# Tracksoar_programmer_shield.net
KiCad netlist of a schematic drawn in EAGLE
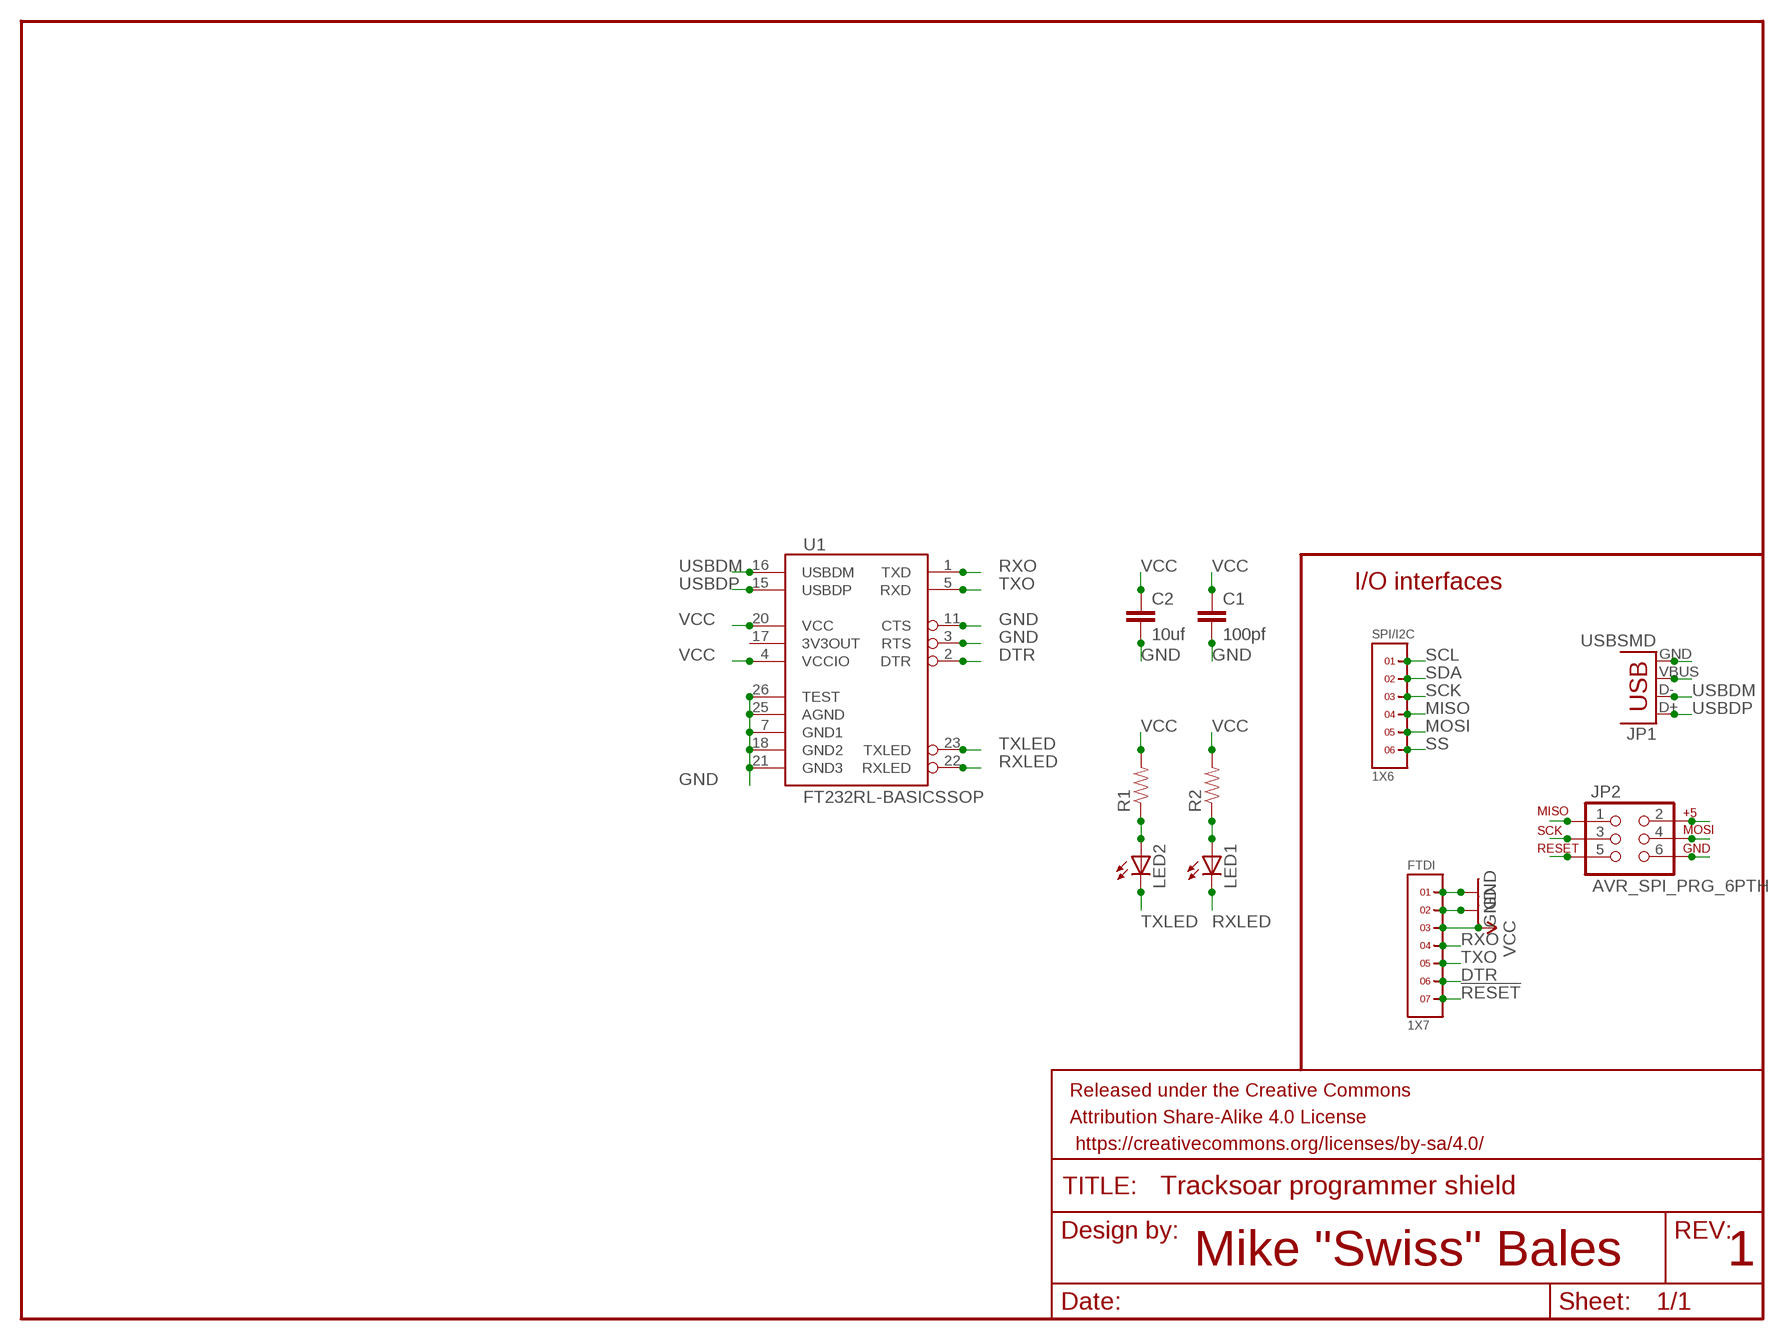
[diagram p0: schematic, sheet 1]

(export (version "E")
  (design (tool "Eeschema 10.0.6"))
  (components
    (comp (ref "C1")
      (value "100pf")
      (footprint "eagle-import:0805")
      (libsource (lib "eagle-import") (part "CAP0805"))
    )
    (comp (ref "C2")
      (value "10uf")
      (footprint "eagle-import:0805")
      (libsource (lib "eagle-import") (part "CAP0805"))
    )
    (comp (ref "FRAME1")
      (value "FRAME-LETTER")
      (footprint "eagle-import:CREATIVE_COMMONS")
      (libsource (lib "eagle-import") (part "FRAME-LETTER"))
    )
    (comp (ref "FTDI")
      (value "1X7")
      (footprint "eagle-import:1X7")
      (libsource (lib "eagle-import") (part "1X7"))
    )
    (comp (ref "JP1")
      (value "USBSMD")
      (footprint "eagle-import:USB-MINIB")
      (libsource (lib "eagle-import") (part "USBSMD"))
    )
    (comp (ref "JP2")
      (value "AVR_SPI_PRG_6PTH")
      (footprint "eagle-import:2X3")
      (libsource (lib "eagle-import") (part "AVR_SPI_PRG_6PTH"))
    )
    (comp (ref "LED1")
      (value "LEDCHIP-LED0805")
      (footprint "eagle-import:CHIP-LED0805")
      (libsource (lib "eagle-import") (part "LEDCHIP-LED0805"))
    )
    (comp (ref "LED2")
      (value "LEDCHIP-LED0805")
      (footprint "eagle-import:CHIP-LED0805")
      (libsource (lib "eagle-import") (part "LEDCHIP-LED0805"))
    )
    (comp (ref "R1")
      (value "RESISTOR0805-RES")
      (footprint "eagle-import:0805")
      (libsource (lib "eagle-import") (part "RESISTOR0805-RES"))
    )
    (comp (ref "R2")
      (value "RESISTOR0805-RES")
      (footprint "eagle-import:0805")
      (libsource (lib "eagle-import") (part "RESISTOR0805-RES"))
    )
    (comp (ref "SPI/I2C")
      (value "1X6")
      (footprint "eagle-import:1X6")
      (libsource (lib "eagle-import") (part "1X6"))
    )
    (comp (ref "U1")
      (value "FT232RL-BASICSSOP")
      (footprint "eagle-import:SSOP28DB")
      (libsource (lib "eagle-import") (part "FT232RL-BASICSSOP"))
    )
  )
  (nets
    (net (code "1") (name "/DTR") (class "Default")
      (node (ref "FTDI") (pin "6") (pinfunction "6_6") (pintype "bidirectional"))
      (node (ref "U1") (pin "2") (pinfunction "DTR_2") (pintype "bidirectional"))
    )
    (net (code "2") (name "/MISO") (class "Default")
      (node (ref "JP2") (pin "1") (pinfunction "1_1") (pintype "passive"))
      (node (ref "SPI/I2C") (pin "4") (pinfunction "4_4") (pintype "bidirectional"))
    )
    (net (code "3") (name "/MOSI") (class "Default")
      (node (ref "JP2") (pin "4") (pinfunction "4_4") (pintype "passive"))
      (node (ref "SPI/I2C") (pin "5") (pinfunction "5_5") (pintype "bidirectional"))
    )
    (net (code "4") (name "/RXLED") (class "Default")
      (node (ref "LED1") (pin "C") (pinfunction "C_C") (pintype "passive"))
      (node (ref "U1") (pin "22") (pinfunction "RXLED_22") (pintype "bidirectional"))
    )
    (net (code "5") (name "/RXO") (class "Default")
      (node (ref "FTDI") (pin "4") (pinfunction "4_4") (pintype "bidirectional"))
      (node (ref "U1") (pin "1") (pinfunction "TXD_1") (pintype "output"))
    )
    (net (code "6") (name "/SCK") (class "Default")
      (node (ref "JP2") (pin "3") (pinfunction "3_3") (pintype "passive"))
      (node (ref "SPI/I2C") (pin "3") (pinfunction "3_3") (pintype "bidirectional"))
    )
    (net (code "7") (name "/SCL") (class "Default")
      (node (ref "SPI/I2C") (pin "1") (pinfunction "1_1") (pintype "bidirectional"))
    )
    (net (code "8") (name "/SDA") (class "Default")
      (node (ref "SPI/I2C") (pin "2") (pinfunction "2_2") (pintype "bidirectional"))
    )
    (net (code "9") (name "/SS") (class "Default")
      (node (ref "SPI/I2C") (pin "6") (pinfunction "6_6") (pintype "bidirectional"))
    )
    (net (code "10") (name "/TXLED") (class "Default")
      (node (ref "LED2") (pin "C") (pinfunction "C_C") (pintype "passive"))
      (node (ref "U1") (pin "23") (pinfunction "TXLED_23") (pintype "bidirectional"))
    )
    (net (code "11") (name "/TXO") (class "Default")
      (node (ref "FTDI") (pin "5") (pinfunction "5_5") (pintype "bidirectional"))
      (node (ref "U1") (pin "5") (pinfunction "RXD_5") (pintype "input"))
    )
    (net (code "12") (name "/USBDM") (class "Default")
      (node (ref "JP1") (pin "D-") (pinfunction "D-_D-") (pintype "bidirectional"))
      (node (ref "U1") (pin "16") (pinfunction "USBDM_16") (pintype "bidirectional"))
    )
    (net (code "13") (name "/USBDP") (class "Default")
      (node (ref "JP1") (pin "D+") (pinfunction "D+_D+") (pintype "bidirectional"))
      (node (ref "U1") (pin "15") (pinfunction "USBDP_15") (pintype "bidirectional"))
    )
    (net (code "14") (name "/~{RESET}") (class "Default")
      (node (ref "FTDI") (pin "7") (pinfunction "7_7") (pintype "bidirectional"))
      (node (ref "JP2") (pin "5") (pinfunction "5_5") (pintype "passive"))
    )
    (net (code "15") (name "GND") (class "Default")
      (node (ref "C1") (pin "2") (pinfunction "2_2") (pintype "passive"))
      (node (ref "C2") (pin "2") (pinfunction "2_2") (pintype "passive"))
      (node (ref "FTDI") (pin "1") (pinfunction "1_1") (pintype "bidirectional"))
      (node (ref "FTDI") (pin "2") (pinfunction "2_2") (pintype "bidirectional"))
      (node (ref "JP1") (pin "GND") (pinfunction "GND_GND") (pintype "bidirectional"))
      (node (ref "JP2") (pin "6") (pinfunction "6_6") (pintype "passive"))
      (node (ref "U1") (pin "11") (pinfunction "CTS_11") (pintype "bidirectional"))
      (node (ref "U1") (pin "18") (pinfunction "GND2_18") (pintype "power_in"))
      (node (ref "U1") (pin "21") (pinfunction "GND3_21") (pintype "power_in"))
      (node (ref "U1") (pin "25") (pinfunction "AGND_25") (pintype "power_in"))
      (node (ref "U1") (pin "26") (pinfunction "TEST_26") (pintype "input"))
      (node (ref "U1") (pin "3") (pinfunction "RTS_3") (pintype "bidirectional"))
      (node (ref "U1") (pin "7") (pinfunction "GND1_7") (pintype "power_in"))
    )
    (net (code "16") (name "Net-(LED1-PadA)") (class "Default")
      (node (ref "LED1") (pin "A") (pinfunction "A_A") (pintype "passive"))
      (node (ref "R2") (pin "1") (pinfunction "1_1") (pintype "passive"))
    )
    (net (code "17") (name "Net-(LED2-PadA)") (class "Default")
      (node (ref "LED2") (pin "A") (pinfunction "A_A") (pintype "passive"))
      (node (ref "R1") (pin "1") (pinfunction "1_1") (pintype "passive"))
    )
    (net (code "18") (name "VCC") (class "Default")
      (node (ref "C1") (pin "1") (pinfunction "1_1") (pintype "passive"))
      (node (ref "C2") (pin "1") (pinfunction "1_1") (pintype "passive"))
      (node (ref "FTDI") (pin "3") (pinfunction "3_3") (pintype "bidirectional"))
      (node (ref "JP1") (pin "VBUS") (pinfunction "VBUS_VBUS") (pintype "bidirectional"))
      (node (ref "JP2") (pin "2") (pinfunction "2_2") (pintype "passive"))
      (node (ref "R1") (pin "2") (pinfunction "2_2") (pintype "passive"))
      (node (ref "R2") (pin "2") (pinfunction "2_2") (pintype "passive"))
      (node (ref "U1") (pin "20") (pinfunction "VCC_20") (pintype "power_in"))
      (node (ref "U1") (pin "4") (pinfunction "VCCIO_4") (pintype "power_in"))
    )
    (net (code "19") (name "unconnected-(U1-3V3OUT-Pad17)") (class "Default")
      (node (ref "U1") (pin "17") (pinfunction "3V3OUT_17") (pintype "output"))
    )
  )
)
